# RP2040_MainV1_alternateLayout.net
KiCad netlist of a schematic drawn in EAGLE
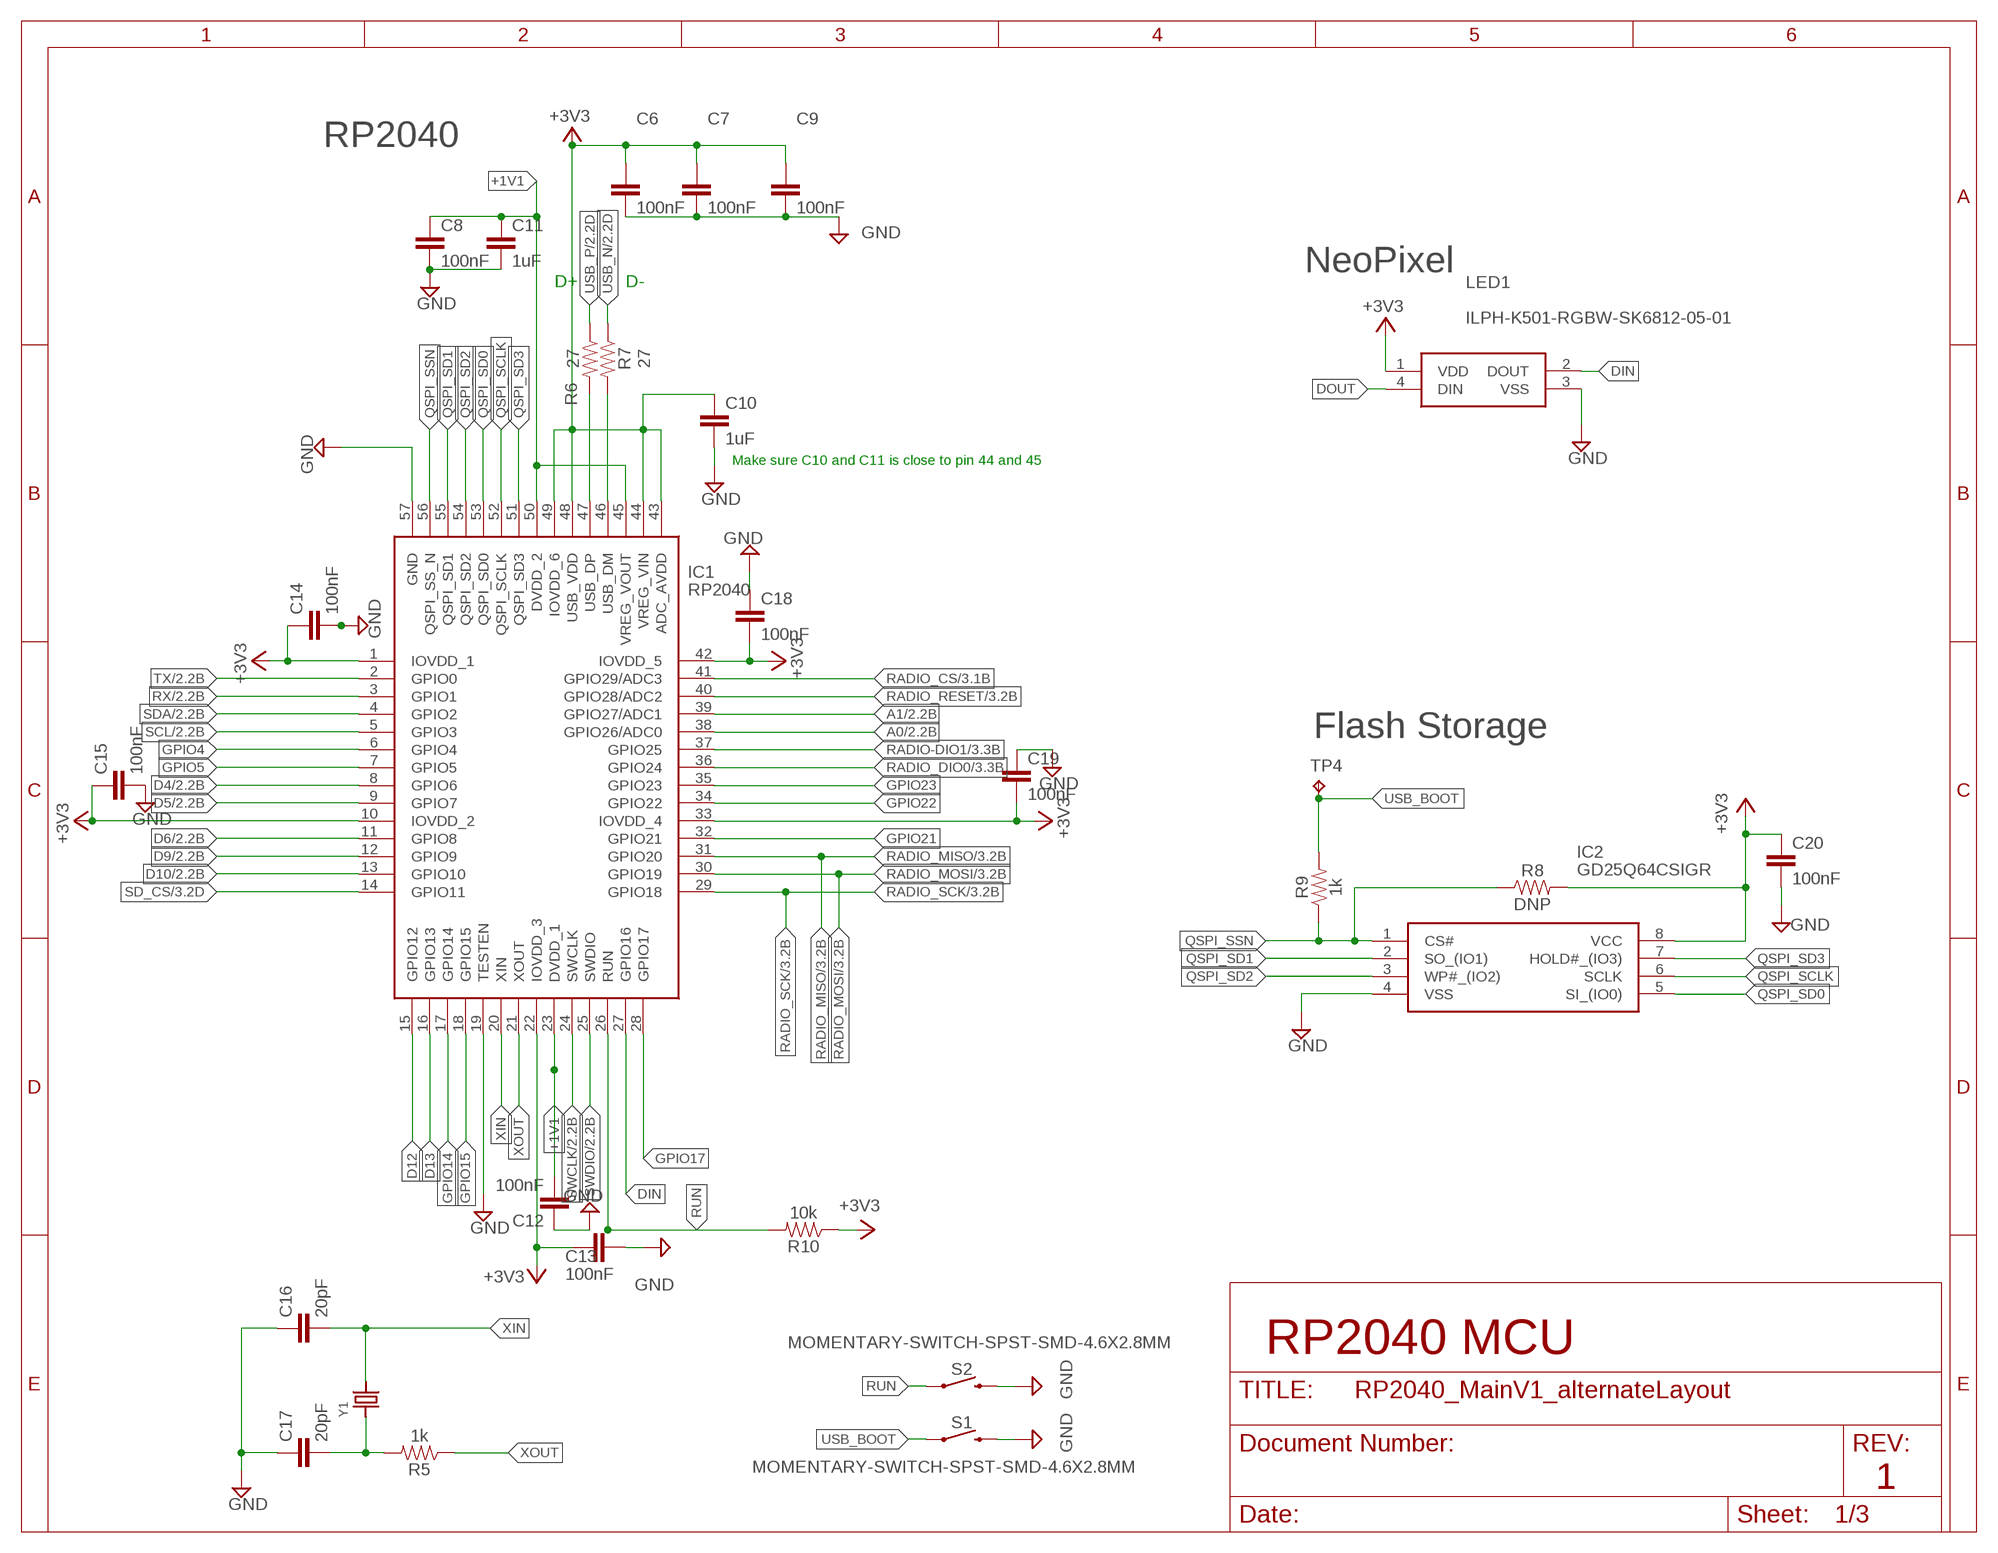
[diagram p0: schematic, sheet 1]
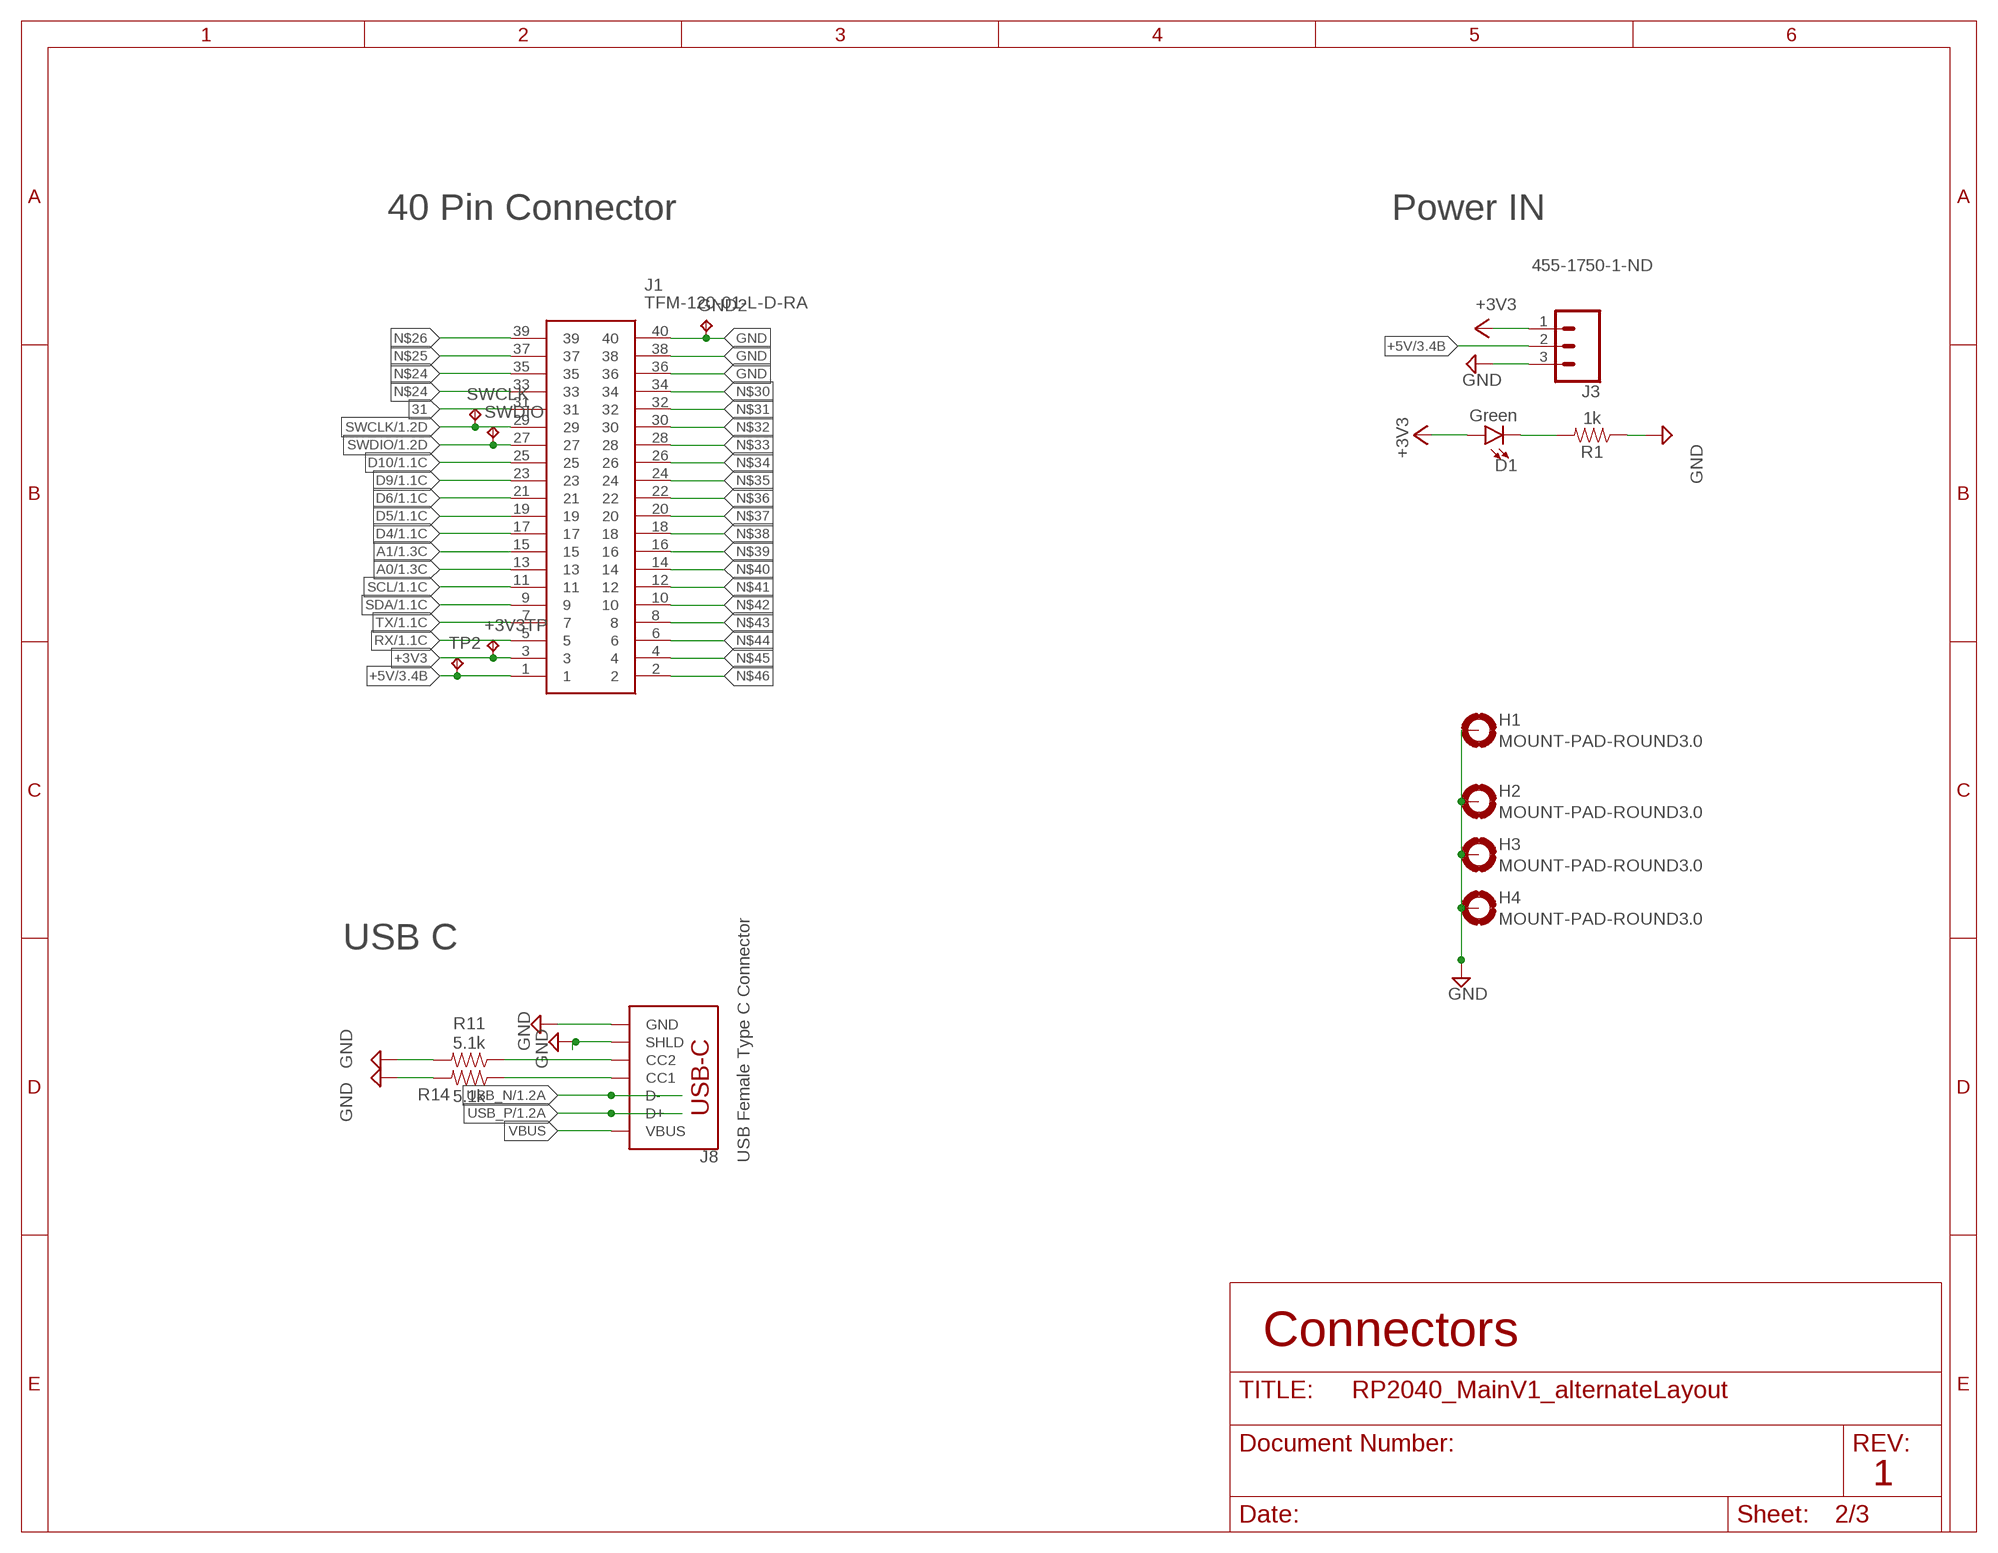
[diagram p1: schematic, sheet 2]
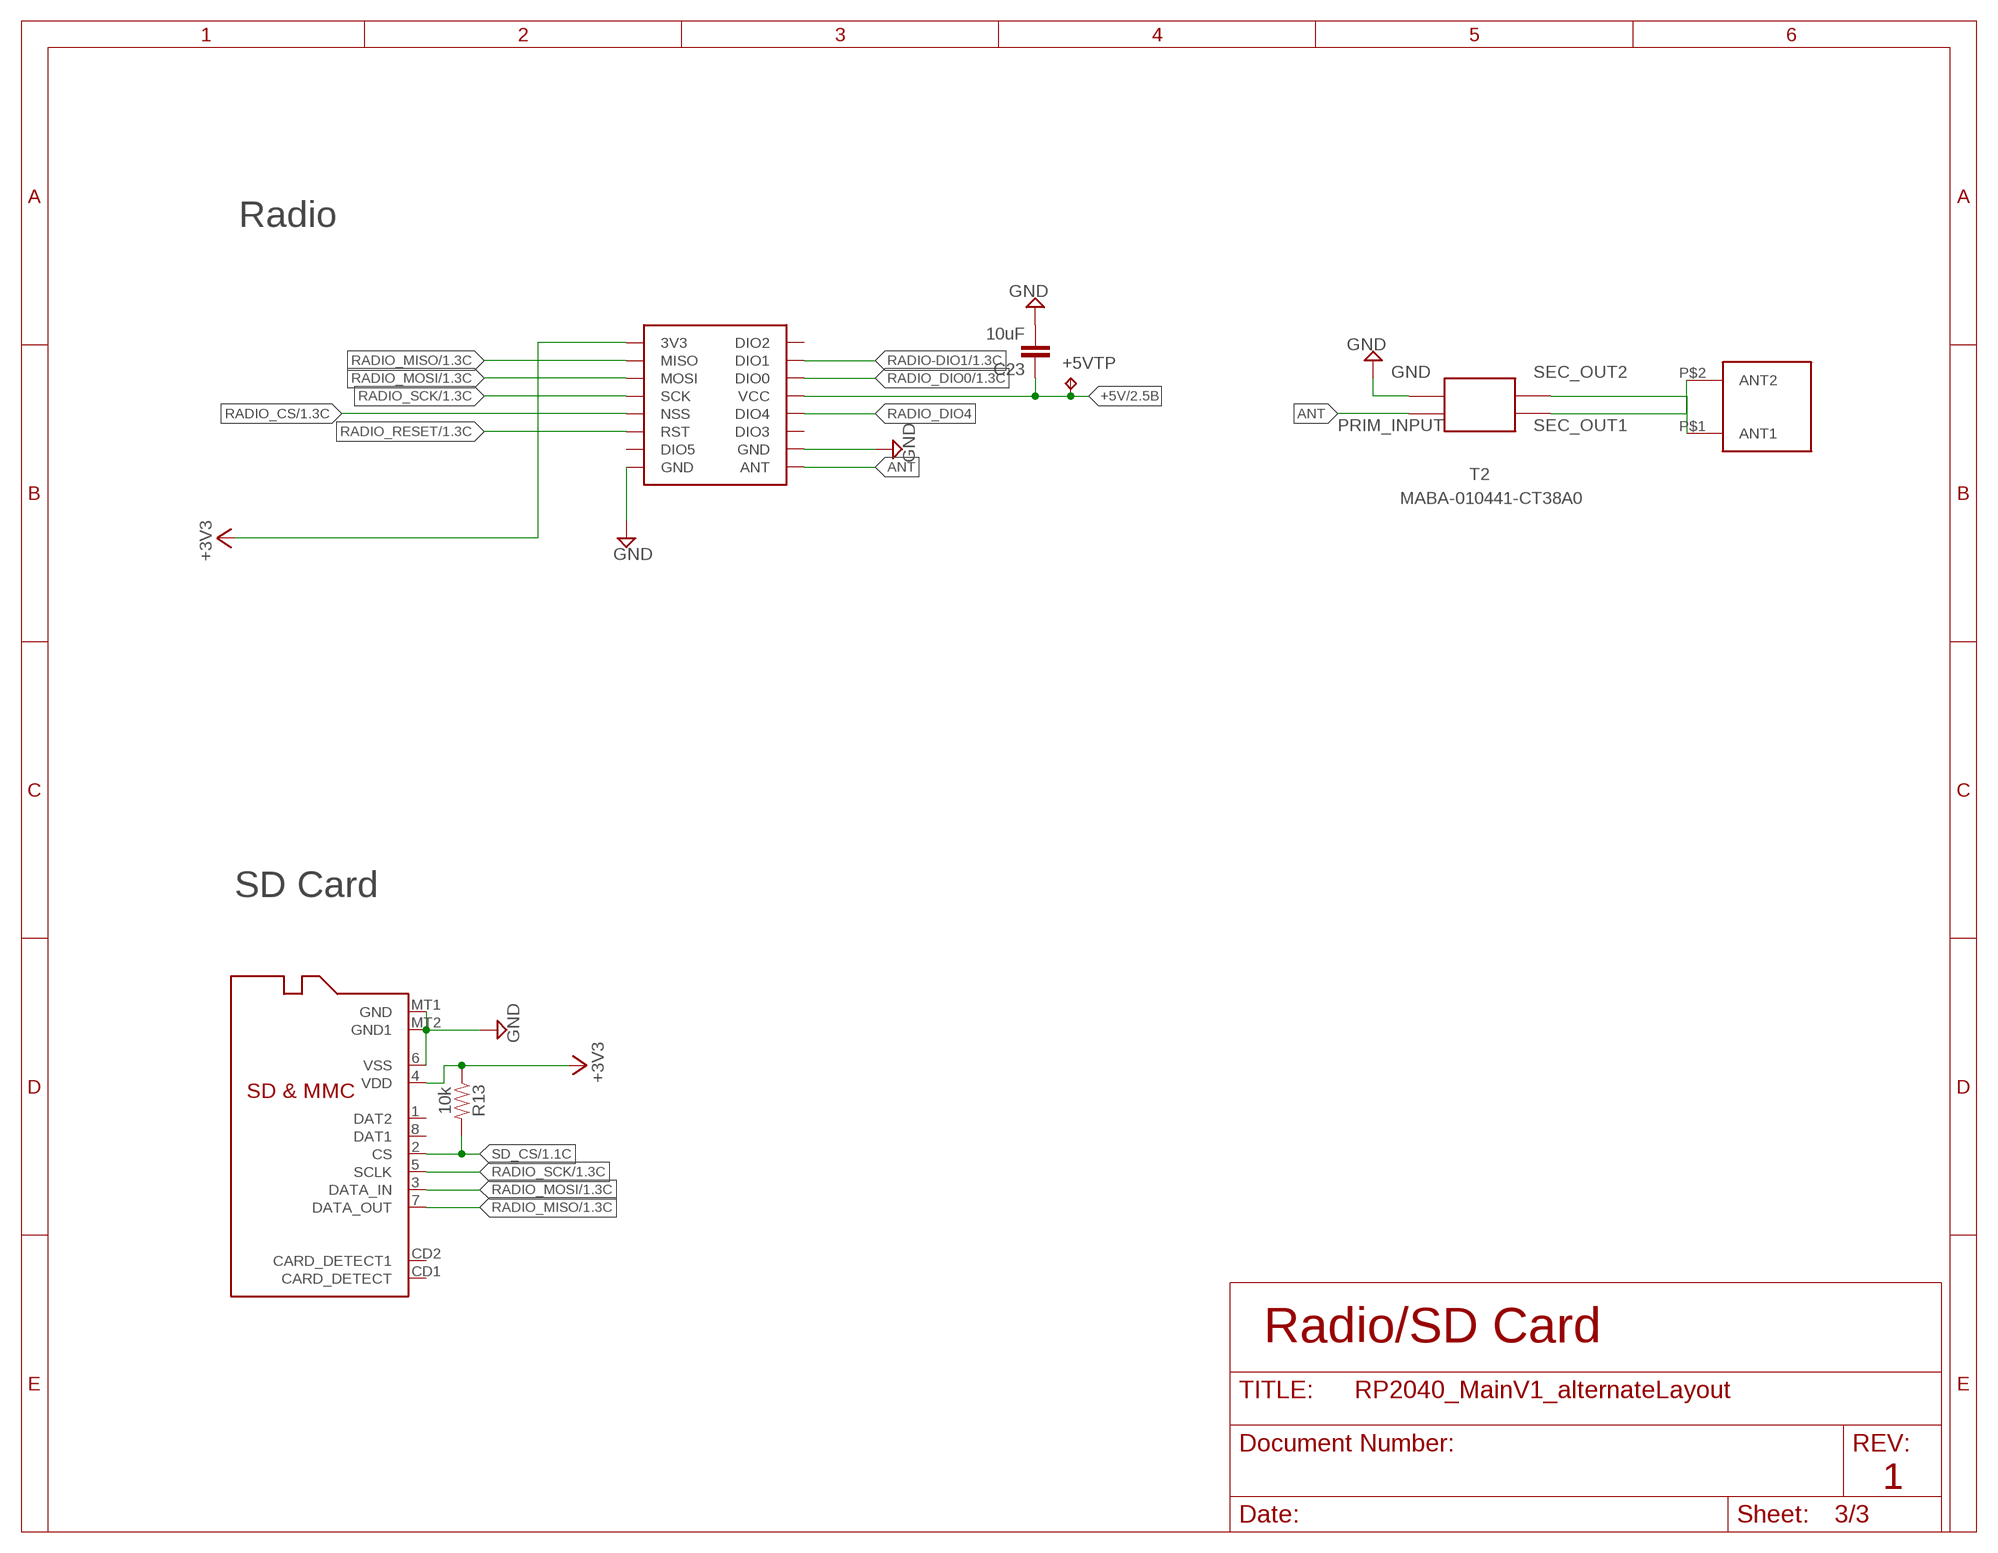
[diagram p2: schematic, sheet 3]

(export (version "E")
  (design (tool "Eeschema 10.0.6"))
  (components
    (comp (ref "C6")
      (value "100nF")
      (footprint "eagle-import:0402")
      (libsource (lib "eagle-import") (part "0.1UF-0402-10V-10%-X7R"))
    )
    (comp (ref "C7")
      (value "100nF")
      (footprint "eagle-import:0402")
      (libsource (lib "eagle-import") (part "0.1UF-0402-10V-10%-X7R"))
    )
    (comp (ref "C8")
      (value "100nF")
      (footprint "eagle-import:0402")
      (libsource (lib "eagle-import") (part "0.1UF-0402-10V-10%-X7R"))
    )
    (comp (ref "C9")
      (value "100nF")
      (footprint "eagle-import:0402")
      (libsource (lib "eagle-import") (part "0.1UF-0402-10V-10%-X7R"))
    )
    (comp (ref "C10")
      (value "1uF")
      (footprint "eagle-import:0402")
      (libsource (lib "eagle-import") (part "0.1UF-0402-10V-10%-X7R"))
    )
    (comp (ref "C11")
      (value "1uF")
      (footprint "eagle-import:0402")
      (libsource (lib "eagle-import") (part "0.1UF-0402-10V-10%-X7R"))
    )
    (comp (ref "C12")
      (value "100nF")
      (footprint "eagle-import:0402")
      (libsource (lib "eagle-import") (part "0.1UF-0402-10V-10%-X7R"))
    )
    (comp (ref "C13")
      (value "100nF")
      (footprint "eagle-import:0402")
      (libsource (lib "eagle-import") (part "0.1UF-0402-10V-10%-X7R"))
    )
    (comp (ref "C14")
      (value "100nF")
      (footprint "eagle-import:0402")
      (libsource (lib "eagle-import") (part "0.1UF-0402-10V-10%-X7R"))
    )
    (comp (ref "C15")
      (value "100nF")
      (footprint "eagle-import:0402")
      (libsource (lib "eagle-import") (part "0.1UF-0402-10V-10%-X7R"))
    )
    (comp (ref "C16")
      (value "20pF")
      (footprint "eagle-import:0603")
      (libsource (lib "eagle-import") (part "10NF-0603-50V-10%"))
    )
    (comp (ref "C17")
      (value "20pF")
      (footprint "eagle-import:0603")
      (libsource (lib "eagle-import") (part "10NF-0603-50V-10%"))
    )
    (comp (ref "C18")
      (value "100nF")
      (footprint "eagle-import:0402")
      (libsource (lib "eagle-import") (part "0.1UF-0402-10V-10%-X7R"))
    )
    (comp (ref "C19")
      (value "100nF")
      (footprint "eagle-import:0402")
      (libsource (lib "eagle-import") (part "0.1UF-0402-10V-10%-X7R"))
    )
    (comp (ref "C20")
      (value "100nF")
      (footprint "eagle-import:0603")
      (libsource (lib "eagle-import") (part "0.1UF-0603-25V-(+80/-20%)"))
    )
    (comp (ref "IC1")
      (value "RP2040")
      (footprint "eagle-import:QFN40P700X700X90-57N")
      (libsource (lib "eagle-import") (part "RP2040"))
    )
    (comp (ref "IC2")
      (value "GD25Q64CSIGR")
      (footprint "eagle-import:SOIC127P790X216-8N")
      (fields (field (name "MOUSER_PART_NUMBER") "363-GD25Q64CSIGR"))
      (libsource (lib "eagle-import") (part "GD25Q64CSIGR"))
    )
    (comp (ref "LED1")
      (value "ILPH-K501-RGBW-SK6812-05-01")
      (footprint "eagle-import:ILPHK501RGBWSK68120501")
      (libsource (lib "eagle-import") (part "ILPH-K501-RGBW-SK6812-05-01"))
    )
    (comp (ref "R5")
      (value "1k")
      (footprint "eagle-import:0603")
      (libsource (lib "eagle-import") (part "0.05OHM-0603-1/5W-1%"))
    )
    (comp (ref "R6")
      (value "27")
      (footprint "eagle-import:0603")
      (libsource (lib "eagle-import") (part "0.05OHM-0603-1/5W-1%"))
    )
    (comp (ref "R7")
      (value "27")
      (footprint "eagle-import:0603")
      (libsource (lib "eagle-import") (part "0.05OHM-0603-1/5W-1%"))
    )
    (comp (ref "R8")
      (value "DNP")
      (footprint "eagle-import:0603")
      (libsource (lib "eagle-import") (part "0.05OHM-0603-1/5W-1%"))
    )
    (comp (ref "R9")
      (value "1k")
      (footprint "eagle-import:0603")
      (libsource (lib "eagle-import") (part "0.05OHM-0603-1/5W-1%"))
    )
    (comp (ref "R10")
      (value "10k")
      (footprint "eagle-import:0603")
      (libsource (lib "eagle-import") (part "0.05OHM-0603-1/5W-1%"))
    )
    (comp (ref "S1")
      (value "MOMENTARY-SWITCH-SPST-SMD-4.6X2.8MM")
      (footprint "eagle-import:TACTILE_SWITCH_SMD_4.6X2.8MM")
      (libsource (lib "eagle-import") (part "MOMENTARY-SWITCH-SPST-SMD-4.6X2.8MM"))
    )
    (comp (ref "S2")
      (value "MOMENTARY-SWITCH-SPST-SMD-4.6X2.8MM")
      (footprint "eagle-import:TACTILE_SWITCH_SMD_4.6X2.8MM")
      (libsource (lib "eagle-import") (part "MOMENTARY-SWITCH-SPST-SMD-4.6X2.8MM"))
    )
    (comp (ref "TP4")
      (value "TPTP12R")
      (footprint "eagle-import:TP12R")
      (libsource (lib "eagle-import") (part "TPTP12R"))
    )
    (comp (ref "Y1")
      (value "CRYSTAL2.5X2.0MM")
      (footprint "eagle-import:CRYSTAL_2.5X2")
      (libsource (lib "eagle-import") (part "CRYSTAL2.5X2.0MM"))
    )
    (comp (ref "+3V3TP")
      (value "TPTP12R")
      (footprint "eagle-import:TP12R")
      (libsource (lib "eagle-import") (part "TPTP12R"))
    )
    (comp (ref "D1")
      (value "Green")
      (footprint "eagle-import:LED-0603")
      (libsource (lib "eagle-import") (part "LED-GREEN-0603-WE"))
    )
    (comp (ref "GND2")
      (value "TPTP12R")
      (footprint "eagle-import:TP12R")
      (libsource (lib "eagle-import") (part "TPTP12R"))
    )
    (comp (ref "H1")
      (value "MOUNT-PAD-ROUND3.0")
      (footprint "eagle-import:3,0-PAD")
      (libsource (lib "eagle-import") (part "MOUNT-PAD-ROUND3.0"))
    )
    (comp (ref "H2")
      (value "MOUNT-PAD-ROUND3.0")
      (footprint "eagle-import:3,0-PAD")
      (libsource (lib "eagle-import") (part "MOUNT-PAD-ROUND3.0"))
    )
    (comp (ref "H3")
      (value "MOUNT-PAD-ROUND3.0")
      (footprint "eagle-import:3,0-PAD")
      (libsource (lib "eagle-import") (part "MOUNT-PAD-ROUND3.0"))
    )
    (comp (ref "H4")
      (value "MOUNT-PAD-ROUND3.0")
      (footprint "eagle-import:3,0-PAD")
      (libsource (lib "eagle-import") (part "MOUNT-PAD-ROUND3.0"))
    )
    (comp (ref "J1")
      (value "TFM-120-01-L-D-RA")
      (footprint "eagle-import:TFM-120-01-XXX-D-RA")
      (fields (field (name "MOUSER_PART_NUMBER") "200-TFM12001LDRA"))
      (libsource (lib "eagle-import") (part "TFM-120-01-L-D-RA"))
    )
    (comp (ref "J3")
      (value "455-1750-1-ND")
      (footprint "eagle-import:1X03")
      (libsource (lib "eagle-import") (part "CONN_03"))
    )
    (comp (ref "J8")
      (value "USB Female Type C Connector")
      (footprint "eagle-import:USB-C-16P-4LAYER-ISOLATED")
      (libsource (lib "eagle-import") (part "USB_C_4-LAYER-ISOLATED"))
    )
    (comp (ref "R1")
      (value "1k")
      (footprint "eagle-import:0603")
      (libsource (lib "eagle-import") (part "0.05OHM-0603-1/5W-1%"))
    )
    (comp (ref "R11")
      (value "5.1k")
      (footprint "eagle-import:0603")
      (libsource (lib "eagle-import") (part "0.05OHM-0603-1/5W-1%"))
    )
    (comp (ref "R14")
      (value "5.1k")
      (footprint "eagle-import:0603")
      (libsource (lib "eagle-import") (part "0.05OHM-0603-1/5W-1%"))
    )
    (comp (ref "SWCLK")
      (value "TPTP12R")
      (footprint "eagle-import:TP12R")
      (libsource (lib "eagle-import") (part "TPTP12R"))
    )
    (comp (ref "SWDIO")
      (value "TPTP12R")
      (footprint "eagle-import:TP12R")
      (libsource (lib "eagle-import") (part "TPTP12R"))
    )
    (comp (ref "TP2")
      (value "TPTP12R")
      (footprint "eagle-import:TP12R")
      (libsource (lib "eagle-import") (part "TPTP12R"))
    )
    (comp (ref "+5VTP")
      (value "TPTP12R")
      (footprint "eagle-import:TP12R")
      (libsource (lib "eagle-import") (part "TPTP12R"))
    )
    (comp (ref "C23")
      (value "10uF")
      (footprint "eagle-import:0603")
      (libsource (lib "eagle-import") (part "10UF-0603-6.3V-20%"))
    )
    (comp (ref "R13")
      (value "10k")
      (footprint "eagle-import:0603")
      (libsource (lib "eagle-import") (part "0.05OHM-0603-1/5W-1%"))
    )
    (comp (ref "T2")
      (value "MABA-010441-CT38A0")
      (footprint "eagle-import:MABA010441CT38A0")
      (fields (field (name "MOUSER_PART_NUMBER") "937-MABA10441-CT38A0"))
      (libsource (lib "eagle-import") (part "MABA-010441-CT38A0"))
    )
    (comp (ref "U$1")
      (value "MICROSD")
      (footprint "eagle-import:MICROSD")
      (libsource (lib "eagle-import") (part "MICROSD"))
    )
    (comp (ref "U$2")
      (value "RFM95W")
      (footprint "eagle-import:RFM95PW")
      (libsource (lib "eagle-import") (part "RFM95W"))
    )
    (comp (ref "U$4")
      (value "BIGPAD")
      (footprint "eagle-import:BIGPADS")
      (libsource (lib "eagle-import") (part "BIGPAD"))
    )
  )
  (nets
    (net (code "1") (name "+1V1") (class "Default")
      (node (ref "C11") (pin "1") (pinfunction "1_1") (pintype "passive"))
      (node (ref "C12") (pin "2") (pinfunction "2_2") (pintype "passive"))
      (node (ref "C8") (pin "1") (pinfunction "1_1") (pintype "passive"))
      (node (ref "IC1") (pin "23") (pinfunction "DVDD_1_23") (pintype "bidirectional"))
      (node (ref "IC1") (pin "45") (pinfunction "VREG_VOUT_45") (pintype "bidirectional"))
      (node (ref "IC1") (pin "50") (pinfunction "DVDD_2_50") (pintype "bidirectional"))
    )
    (net (code "2") (name "+3V3") (class "Default")
      (node (ref "+3V3TP") (pin "TP") (pinfunction "TP_TP") (pintype "input"))
      (node (ref "C10") (pin "1") (pinfunction "1_1") (pintype "passive"))
      (node (ref "C13") (pin "2") (pinfunction "2_2") (pintype "passive"))
      (node (ref "C14") (pin "1") (pinfunction "1_1") (pintype "passive"))
      (node (ref "C15") (pin "1") (pinfunction "1_1") (pintype "passive"))
      (node (ref "C18") (pin "2") (pinfunction "2_2") (pintype "passive"))
      (node (ref "C19") (pin "2") (pinfunction "2_2") (pintype "passive"))
      (node (ref "C20") (pin "1") (pinfunction "1_1") (pintype "passive"))
      (node (ref "C6") (pin "1") (pinfunction "1_1") (pintype "passive"))
      (node (ref "C7") (pin "1") (pinfunction "1_1") (pintype "passive"))
      (node (ref "C9") (pin "1") (pinfunction "1_1") (pintype "passive"))
      (node (ref "D1") (pin "A") (pinfunction "A_A") (pintype "passive"))
      (node (ref "IC1") (pin "1") (pinfunction "IOVDD_1_1") (pintype "bidirectional"))
      (node (ref "IC1") (pin "10") (pinfunction "IOVDD_2_10") (pintype "bidirectional"))
      (node (ref "IC1") (pin "22") (pinfunction "IOVDD_3_22") (pintype "bidirectional"))
      (node (ref "IC1") (pin "33") (pinfunction "IOVDD_4_33") (pintype "bidirectional"))
      (node (ref "IC1") (pin "42") (pinfunction "IOVDD_5_42") (pintype "bidirectional"))
      (node (ref "IC1") (pin "43") (pinfunction "ADC_AVDD_43") (pintype "bidirectional"))
      (node (ref "IC1") (pin "44") (pinfunction "VREG_VIN_44") (pintype "bidirectional"))
      (node (ref "IC1") (pin "48") (pinfunction "USB_VDD_48") (pintype "bidirectional"))
      (node (ref "IC1") (pin "49") (pinfunction "IOVDD_6_49") (pintype "bidirectional"))
      (node (ref "IC2") (pin "8") (pinfunction "VCC_8") (pintype "bidirectional"))
      (node (ref "J1") (pin "3") (pinfunction "3_3") (pintype "bidirectional"))
      (node (ref "J3") (pin "1") (pinfunction "1_1") (pintype "passive"))
      (node (ref "LED1") (pin "1") (pinfunction "VDD_1") (pintype "bidirectional"))
      (node (ref "R10") (pin "1") (pinfunction "1_1") (pintype "passive"))
      (node (ref "R13") (pin "1") (pinfunction "1_1") (pintype "passive"))
      (node (ref "R8") (pin "2") (pinfunction "2_2") (pintype "passive"))
      (node (ref "U$1") (pin "4") (pinfunction "VDD_4") (pintype "power_in"))
      (node (ref "U$2") (pin "3V3") (pinfunction "3V3_3V3") (pintype "power_in"))
    )
    (net (code "3") (name "+5V") (class "Default")
      (node (ref "+5VTP") (pin "TP") (pinfunction "TP_TP") (pintype "input"))
      (node (ref "C23") (pin "1") (pinfunction "1_1") (pintype "passive"))
      (node (ref "J1") (pin "1") (pinfunction "1_1") (pintype "bidirectional"))
      (node (ref "J3") (pin "2") (pinfunction "2_2") (pintype "passive"))
      (node (ref "TP2") (pin "TP") (pinfunction "TP_TP") (pintype "input"))
      (node (ref "U$2") (pin "VCC") (pinfunction "VCC_VCC") (pintype "power_in"))
    )
    (net (code "4") (name "31") (class "Default")
      (node (ref "J1") (pin "31") (pinfunction "31_31") (pintype "bidirectional"))
    )
    (net (code "5") (name "A0") (class "Default")
      (node (ref "IC1") (pin "38") (pinfunction "GPIO26/ADC0_38") (pintype "bidirectional"))
      (node (ref "J1") (pin "13") (pinfunction "13_13") (pintype "bidirectional"))
    )
    (net (code "6") (name "A1") (class "Default")
      (node (ref "IC1") (pin "39") (pinfunction "GPIO27/ADC1_39") (pintype "bidirectional"))
      (node (ref "J1") (pin "15") (pinfunction "15_15") (pintype "bidirectional"))
    )
    (net (code "7") (name "ANT") (class "Default")
      (node (ref "T2") (pin "1") (pinfunction "PRIMARY_DOT_(INPUT)_1") (pintype "bidirectional"))
      (node (ref "U$2") (pin "ANT") (pinfunction "ANT_ANT") (pintype "bidirectional"))
    )
    (net (code "8") (name "D4") (class "Default")
      (node (ref "IC1") (pin "8") (pinfunction "GPIO6_8") (pintype "bidirectional"))
      (node (ref "J1") (pin "17") (pinfunction "17_17") (pintype "bidirectional"))
    )
    (net (code "9") (name "D5") (class "Default")
      (node (ref "IC1") (pin "9") (pinfunction "GPIO7_9") (pintype "bidirectional"))
      (node (ref "J1") (pin "19") (pinfunction "19_19") (pintype "bidirectional"))
    )
    (net (code "10") (name "D6") (class "Default")
      (node (ref "IC1") (pin "11") (pinfunction "GPIO8_11") (pintype "bidirectional"))
      (node (ref "J1") (pin "21") (pinfunction "21_21") (pintype "bidirectional"))
    )
    (net (code "11") (name "D9") (class "Default")
      (node (ref "IC1") (pin "12") (pinfunction "GPIO9_12") (pintype "bidirectional"))
      (node (ref "J1") (pin "23") (pinfunction "23_23") (pintype "bidirectional"))
    )
    (net (code "12") (name "D10") (class "Default")
      (node (ref "IC1") (pin "13") (pinfunction "GPIO10_13") (pintype "bidirectional"))
      (node (ref "J1") (pin "25") (pinfunction "25_25") (pintype "bidirectional"))
    )
    (net (code "13") (name "D12") (class "Default")
      (node (ref "IC1") (pin "15") (pinfunction "GPIO12_15") (pintype "bidirectional"))
    )
    (net (code "14") (name "D13") (class "Default")
      (node (ref "IC1") (pin "16") (pinfunction "GPIO13_16") (pintype "bidirectional"))
    )
    (net (code "15") (name "DIN") (class "Default")
      (node (ref "IC1") (pin "27") (pinfunction "GPIO16_27") (pintype "bidirectional"))
      (node (ref "LED1") (pin "2") (pinfunction "DOUT_2") (pintype "bidirectional"))
    )
    (net (code "16") (name "DOUT") (class "Default")
      (node (ref "LED1") (pin "4") (pinfunction "DIN_4") (pintype "bidirectional"))
    )
    (net (code "17") (name "GND") (class "Default")
      (node (ref "C10") (pin "2") (pinfunction "2_2") (pintype "passive"))
      (node (ref "C11") (pin "2") (pinfunction "2_2") (pintype "passive"))
      (node (ref "C12") (pin "1") (pinfunction "1_1") (pintype "passive"))
      (node (ref "C13") (pin "1") (pinfunction "1_1") (pintype "passive"))
      (node (ref "C14") (pin "2") (pinfunction "2_2") (pintype "passive"))
      (node (ref "C15") (pin "2") (pinfunction "2_2") (pintype "passive"))
      (node (ref "C16") (pin "1") (pinfunction "1_1") (pintype "passive"))
      (node (ref "C17") (pin "1") (pinfunction "1_1") (pintype "passive"))
      (node (ref "C18") (pin "1") (pinfunction "1_1") (pintype "passive"))
      (node (ref "C19") (pin "1") (pinfunction "1_1") (pintype "passive"))
      (node (ref "C20") (pin "2") (pinfunction "2_2") (pintype "passive"))
      (node (ref "C23") (pin "2") (pinfunction "2_2") (pintype "passive"))
      (node (ref "C6") (pin "2") (pinfunction "2_2") (pintype "passive"))
      (node (ref "C7") (pin "2") (pinfunction "2_2") (pintype "passive"))
      (node (ref "C8") (pin "2") (pinfunction "2_2") (pintype "passive"))
      (node (ref "C9") (pin "2") (pinfunction "2_2") (pintype "passive"))
      (node (ref "GND2") (pin "TP") (pinfunction "TP_TP") (pintype "input"))
      (node (ref "H1") (pin "B3,0") (pinfunction "MOUNT_B3,0") (pintype "passive"))
      (node (ref "H2") (pin "B3,0") (pinfunction "MOUNT_B3,0") (pintype "passive"))
      (node (ref "H3") (pin "B3,0") (pinfunction "MOUNT_B3,0") (pintype "passive"))
      (node (ref "H4") (pin "B3,0") (pinfunction "MOUNT_B3,0") (pintype "passive"))
      (node (ref "IC1") (pin "19") (pinfunction "TESTEN_19") (pintype "bidirectional"))
      (node (ref "IC1") (pin "57") (pinfunction "GND_57") (pintype "bidirectional"))
      (node (ref "IC2") (pin "4") (pinfunction "VSS_4") (pintype "bidirectional"))
      (node (ref "J1") (pin "36") (pinfunction "36_36") (pintype "bidirectional"))
      (node (ref "J1") (pin "38") (pinfunction "38_38") (pintype "bidirectional"))
      (node (ref "J1") (pin "40") (pinfunction "40_40") (pintype "bidirectional"))
      (node (ref "J3") (pin "3") (pinfunction "3_3") (pintype "passive"))
      (node (ref "J8") (pin "GND") (pinfunction "GND_GND") (pintype "bidirectional"))
      (node (ref "J8") (pin "GND2") (pinfunction "GND_GND2") (pintype "bidirectional"))
      (node (ref "J8") (pin "SHLD1") (pinfunction "SHLD_SHLD1") (pintype "bidirectional"))
      (node (ref "J8") (pin "SHLD2") (pinfunction "SHLD_SHLD2") (pintype "bidirectional"))
      (node (ref "J8") (pin "SHLD3") (pinfunction "SHLD_SHLD3") (pintype "bidirectional"))
      (node (ref "J8") (pin "SHLD4") (pinfunction "SHLD_SHLD4") (pintype "bidirectional"))
      (node (ref "J8") (pin "SHLD5") (pinfunction "SHLD_SHLD5") (pintype "bidirectional"))
      (node (ref "J8") (pin "SHLD6") (pinfunction "SHLD_SHLD6") (pintype "bidirectional"))
      (node (ref "J8") (pin "SHLD7") (pinfunction "SHLD_SHLD7") (pintype "bidirectional"))
      (node (ref "J8") (pin "SHLD8") (pinfunction "SHLD_SHLD8") (pintype "bidirectional"))
      (node (ref "LED1") (pin "3") (pinfunction "VSS_3") (pintype "bidirectional"))
      (node (ref "R1") (pin "1") (pinfunction "1_1") (pintype "passive"))
      (node (ref "R11") (pin "2") (pinfunction "2_2") (pintype "passive"))
      (node (ref "R14") (pin "2") (pinfunction "2_2") (pintype "passive"))
      (node (ref "S1") (pin "3") (pinfunction "2_3") (pintype "passive"))
      (node (ref "S1") (pin "4") (pinfunction "2_4") (pintype "passive"))
      (node (ref "S2") (pin "3") (pinfunction "2_3") (pintype "passive"))
      (node (ref "S2") (pin "4") (pinfunction "2_4") (pintype "passive"))
      (node (ref "T2") (pin "4") (pinfunction "PRIMARY_(GROUND)_4") (pintype "bidirectional"))
      (node (ref "U$1") (pin "6") (pinfunction "VSS_6") (pintype "power_in"))
      (node (ref "U$1") (pin "MT1") (pinfunction "GND_MT1") (pintype "power_in"))
      (node (ref "U$1") (pin "MT2") (pinfunction "GND1_MT2") (pintype "power_in"))
      (node (ref "U$2") (pin "GND@0") (pinfunction "GND_GND@0") (pintype "power_in"))
      (node (ref "U$2") (pin "GND@1") (pinfunction "GND_GND@1") (pintype "power_in"))
    )
    (net (code "18") (name "GPIO4") (class "Default")
      (node (ref "IC1") (pin "6") (pinfunction "GPIO4_6") (pintype "bidirectional"))
    )
    (net (code "19") (name "GPIO5") (class "Default")
      (node (ref "IC1") (pin "7") (pinfunction "GPIO5_7") (pintype "bidirectional"))
    )
    (net (code "20") (name "GPIO14") (class "Default")
      (node (ref "IC1") (pin "17") (pinfunction "GPIO14_17") (pintype "bidirectional"))
    )
    (net (code "21") (name "GPIO15") (class "Default")
      (node (ref "IC1") (pin "18") (pinfunction "GPIO15_18") (pintype "bidirectional"))
    )
    (net (code "22") (name "GPIO17") (class "Default")
      (node (ref "IC1") (pin "28") (pinfunction "GPIO17_28") (pintype "bidirectional"))
    )
    (net (code "23") (name "GPIO21") (class "Default")
      (node (ref "IC1") (pin "32") (pinfunction "GPIO21_32") (pintype "bidirectional"))
    )
    (net (code "24") (name "GPIO22") (class "Default")
      (node (ref "IC1") (pin "34") (pinfunction "GPIO22_34") (pintype "bidirectional"))
    )
    (net (code "25") (name "GPIO23") (class "Default")
      (node (ref "IC1") (pin "35") (pinfunction "GPIO23_35") (pintype "bidirectional"))
    )
    (net (code "26") (name "N$24") (class "Default")
      (node (ref "J1") (pin "35") (pinfunction "35_35") (pintype "bidirectional"))
    )
    (net (code "27") (name "N$25") (class "Default")
      (node (ref "J1") (pin "37") (pinfunction "37_37") (pintype "bidirectional"))
    )
    (net (code "28") (name "N$26") (class "Default")
      (node (ref "J1") (pin "39") (pinfunction "39_39") (pintype "bidirectional"))
    )
    (net (code "29") (name "N$30") (class "Default")
      (node (ref "J1") (pin "34") (pinfunction "34_34") (pintype "bidirectional"))
    )
    (net (code "30") (name "N$31") (class "Default")
      (node (ref "J1") (pin "32") (pinfunction "32_32") (pintype "bidirectional"))
    )
    (net (code "31") (name "N$32") (class "Default")
      (node (ref "J1") (pin "30") (pinfunction "30_30") (pintype "bidirectional"))
    )
    (net (code "32") (name "N$33") (class "Default")
      (node (ref "J1") (pin "28") (pinfunction "28_28") (pintype "bidirectional"))
    )
    (net (code "33") (name "N$34") (class "Default")
      (node (ref "J1") (pin "26") (pinfunction "26_26") (pintype "bidirectional"))
    )
    (net (code "34") (name "N$35") (class "Default")
      (node (ref "J1") (pin "24") (pinfunction "24_24") (pintype "bidirectional"))
    )
    (net (code "35") (name "N$36") (class "Default")
      (node (ref "J1") (pin "22") (pinfunction "22_22") (pintype "bidirectional"))
    )
    (net (code "36") (name "N$37") (class "Default")
      (node (ref "J1") (pin "20") (pinfunction "20_20") (pintype "bidirectional"))
    )
    (net (code "37") (name "N$38") (class "Default")
      (node (ref "J1") (pin "18") (pinfunction "18_18") (pintype "bidirectional"))
    )
    (net (code "38") (name "N$39") (class "Default")
      (node (ref "J1") (pin "16") (pinfunction "16_16") (pintype "bidirectional"))
    )
    (net (code "39") (name "N$40") (class "Default")
      (node (ref "J1") (pin "14") (pinfunction "14_14") (pintype "bidirectional"))
    )
    (net (code "40") (name "N$41") (class "Default")
      (node (ref "J1") (pin "12") (pinfunction "12_12") (pintype "bidirectional"))
    )
    (net (code "41") (name "N$42") (class "Default")
      (node (ref "J1") (pin "10") (pinfunction "10_10") (pintype "bidirectional"))
    )
    (net (code "42") (name "N$43") (class "Default")
      (node (ref "J1") (pin "8") (pinfunction "8_8") (pintype "bidirectional"))
    )
    (net (code "43") (name "N$44") (class "Default")
      (node (ref "J1") (pin "6") (pinfunction "6_6") (pintype "bidirectional"))
    )
    (net (code "44") (name "N$45") (class "Default")
      (node (ref "J1") (pin "4") (pinfunction "4_4") (pintype "bidirectional"))
    )
    (net (code "45") (name "N$46") (class "Default")
      (node (ref "J1") (pin "2") (pinfunction "2_2") (pintype "bidirectional"))
    )
    (net (code "46") (name "Net-(C17-Pad2)") (class "Default")
      (node (ref "C17") (pin "2") (pinfunction "2_2") (pintype "passive"))
      (node (ref "R5") (pin "2") (pinfunction "2_2") (pintype "passive"))
      (node (ref "Y1") (pin "1") (pinfunction "1_1") (pintype "passive"))
    )
    (net (code "47") (name "Net-(D1-PadC)") (class "Default")
      (node (ref "D1") (pin "C") (pinfunction "C_C") (pintype "passive"))
      (node (ref "R1") (pin "2") (pinfunction "2_2") (pintype "passive"))
    )
    (net (code "48") (name "Net-(IC1-USB_DM)") (class "Default")
      (node (ref "IC1") (pin "46") (pinfunction "USB_DM_46") (pintype "bidirectional"))
      (node (ref "R7") (pin "2") (pinfunction "2_2") (pintype "passive"))
    )
    (net (code "49") (name "Net-(IC1-USB_DP)") (class "Default")
      (node (ref "IC1") (pin "47") (pinfunction "USB_DP_47") (pintype "bidirectional"))
      (node (ref "R6") (pin "2") (pinfunction "2_2") (pintype "passive"))
    )
    (net (code "50") (name "Net-(J8-CC1)") (class "Default")
      (node (ref "J8") (pin "A5") (pinfunction "CC1_A5") (pintype "bidirectional"))
      (node (ref "R14") (pin "1") (pinfunction "1_1") (pintype "passive"))
    )
    (net (code "51") (name "Net-(J8-CC2)") (class "Default")
      (node (ref "J8") (pin "B5") (pinfunction "CC2_B5") (pintype "bidirectional"))
      (node (ref "R11") (pin "1") (pinfunction "1_1") (pintype "passive"))
    )
    (net (code "52") (name "Net-(T2-SECONDARY_(OUTPUT_2))") (class "Default")
      (node (ref "T2") (pin "3") (pinfunction "SECONDARY_(OUTPUT_2)_3") (pintype "bidirectional"))
      (node (ref "U$4") (pin "P$1") (pinfunction "ANT1_P$1") (pintype "bidirectional"))
    )
    (net (code "53") (name "Net-(T2-SECONDARY_DOT_(OUTPUT_1))") (class "Default")
      (node (ref "T2") (pin "2") (pinfunction "SECONDARY_DOT_(OUTPUT_1)_2") (pintype "bidirectional"))
      (node (ref "U$4") (pin "P$2") (pinfunction "ANT2_P$2") (pintype "bidirectional"))
    )
    (net (code "54") (name "QSPI_SCLK") (class "Default")
      (node (ref "IC1") (pin "52") (pinfunction "QSPI_SCLK_52") (pintype "bidirectional"))
      (node (ref "IC2") (pin "6") (pinfunction "SCLK_6") (pintype "bidirectional"))
    )
    (net (code "55") (name "QSPI_SD0") (class "Default")
      (node (ref "IC1") (pin "53") (pinfunction "QSPI_SD0_53") (pintype "bidirectional"))
      (node (ref "IC2") (pin "5") (pinfunction "SI_(IO0)_5") (pintype "bidirectional"))
    )
    (net (code "56") (name "QSPI_SD1") (class "Default")
      (node (ref "IC1") (pin "55") (pinfunction "QSPI_SD1_55") (pintype "bidirectional"))
      (node (ref "IC2") (pin "2") (pinfunction "SO_(IO1)_2") (pintype "bidirectional"))
    )
    (net (code "57") (name "QSPI_SD2") (class "Default")
      (node (ref "IC1") (pin "54") (pinfunction "QSPI_SD2_54") (pintype "bidirectional"))
      (node (ref "IC2") (pin "3") (pinfunction "WP#_(IO2)_3") (pintype "bidirectional"))
    )
    (net (code "58") (name "QSPI_SD3") (class "Default")
      (node (ref "IC1") (pin "51") (pinfunction "QSPI_SD3_51") (pintype "bidirectional"))
      (node (ref "IC2") (pin "7") (pinfunction "HOLD#_(IO3)_7") (pintype "bidirectional"))
    )
    (net (code "59") (name "QSPI_SSN") (class "Default")
      (node (ref "IC1") (pin "56") (pinfunction "QSPI_SS_N_56") (pintype "bidirectional"))
      (node (ref "IC2") (pin "1") (pinfunction "CS#_1") (pintype "bidirectional"))
      (node (ref "R8") (pin "1") (pinfunction "1_1") (pintype "passive"))
      (node (ref "R9") (pin "1") (pinfunction "1_1") (pintype "passive"))
    )
    (net (code "60") (name "RADIO-DIO1") (class "Default")
      (node (ref "IC1") (pin "37") (pinfunction "GPIO25_37") (pintype "bidirectional"))
      (node (ref "U$2") (pin "DIO1") (pinfunction "DIO1_DIO1") (pintype "bidirectional"))
    )
    (net (code "61") (name "RADIO_CS") (class "Default")
      (node (ref "IC1") (pin "41") (pinfunction "GPIO29/ADC3_41") (pintype "bidirectional"))
      (node (ref "U$2") (pin "NSS") (pinfunction "NSS_NSS") (pintype "bidirectional"))
    )
    (net (code "62") (name "RADIO_DIO0") (class "Default")
      (node (ref "IC1") (pin "36") (pinfunction "GPIO24_36") (pintype "bidirectional"))
      (node (ref "U$2") (pin "DIO0") (pinfunction "DIO0_DIO0") (pintype "bidirectional"))
    )
    (net (code "63") (name "RADIO_DIO4") (class "Default")
      (node (ref "U$2") (pin "DIO4") (pinfunction "DIO4_DIO4") (pintype "bidirectional"))
    )
    (net (code "64") (name "RADIO_MISO") (class "Default")
      (node (ref "IC1") (pin "31") (pinfunction "GPIO20_31") (pintype "bidirectional"))
      (node (ref "U$1") (pin "7") (pinfunction "DATA_OUT_7") (pintype "output"))
      (node (ref "U$2") (pin "MISO") (pinfunction "MISO_MISO") (pintype "bidirectional"))
    )
    (net (code "65") (name "RADIO_MOSI") (class "Default")
      (node (ref "IC1") (pin "30") (pinfunction "GPIO19_30") (pintype "bidirectional"))
      (node (ref "U$1") (pin "3") (pinfunction "DATA_IN_3") (pintype "input"))
      (node (ref "U$2") (pin "MOSI") (pinfunction "MOSI_MOSI") (pintype "bidirectional"))
    )
    (net (code "66") (name "RADIO_RESET") (class "Default")
      (node (ref "IC1") (pin "40") (pinfunction "GPIO28/ADC2_40") (pintype "bidirectional"))
      (node (ref "U$2") (pin "RST") (pinfunction "RST_RST") (pintype "bidirectional"))
    )
    (net (code "67") (name "RADIO_SCK") (class "Default")
      (node (ref "IC1") (pin "29") (pinfunction "GPIO18_29") (pintype "bidirectional"))
      (node (ref "U$1") (pin "5") (pinfunction "SCLK_5") (pintype "input"))
      (node (ref "U$2") (pin "SCK") (pinfunction "SCK_SCK") (pintype "bidirectional"))
    )
    (net (code "68") (name "RUN") (class "Default")
      (node (ref "IC1") (pin "26") (pinfunction "RUN_26") (pintype "bidirectional"))
      (node (ref "R10") (pin "2") (pinfunction "2_2") (pintype "passive"))
      (node (ref "S2") (pin "1") (pinfunction "1_1") (pintype "passive"))
      (node (ref "S2") (pin "2") (pinfunction "1_2") (pintype "passive"))
    )
    (net (code "69") (name "RX") (class "Default")
      (node (ref "IC1") (pin "3") (pinfunction "GPIO1_3") (pintype "bidirectional"))
      (node (ref "J1") (pin "5") (pinfunction "5_5") (pintype "bidirectional"))
    )
    (net (code "70") (name "SCL") (class "Default")
      (node (ref "IC1") (pin "5") (pinfunction "GPIO3_5") (pintype "bidirectional"))
      (node (ref "J1") (pin "11") (pinfunction "11_11") (pintype "bidirectional"))
    )
    (net (code "71") (name "SDA") (class "Default")
      (node (ref "IC1") (pin "4") (pinfunction "GPIO2_4") (pintype "bidirectional"))
      (node (ref "J1") (pin "9") (pinfunction "9_9") (pintype "bidirectional"))
    )
    (net (code "72") (name "SD_CS") (class "Default")
      (node (ref "IC1") (pin "14") (pinfunction "GPIO11_14") (pintype "bidirectional"))
      (node (ref "R13") (pin "2") (pinfunction "2_2") (pintype "passive"))
      (node (ref "U$1") (pin "2") (pinfunction "CS_2") (pintype "input"))
    )
    (net (code "73") (name "SWCLK") (class "Default")
      (node (ref "IC1") (pin "24") (pinfunction "SWCLK_24") (pintype "bidirectional"))
      (node (ref "J1") (pin "29") (pinfunction "29_29") (pintype "bidirectional"))
      (node (ref "SWCLK") (pin "TP") (pinfunction "TP_TP") (pintype "input"))
    )
    (net (code "74") (name "SWDIO") (class "Default")
      (node (ref "IC1") (pin "25") (pinfunction "SWDIO_25") (pintype "bidirectional"))
      (node (ref "J1") (pin "27") (pinfunction "27_27") (pintype "bidirectional"))
      (node (ref "SWDIO") (pin "TP") (pinfunction "TP_TP") (pintype "input"))
    )
    (net (code "75") (name "TX") (class "Default")
      (node (ref "IC1") (pin "2") (pinfunction "GPIO0_2") (pintype "bidirectional"))
      (node (ref "J1") (pin "7") (pinfunction "7_7") (pintype "bidirectional"))
    )
    (net (code "76") (name "USB_BOOT") (class "Default")
      (node (ref "R9") (pin "2") (pinfunction "2_2") (pintype "passive"))
      (node (ref "S1") (pin "1") (pinfunction "1_1") (pintype "passive"))
      (node (ref "S1") (pin "2") (pinfunction "1_2") (pintype "passive"))
      (node (ref "TP4") (pin "TP") (pinfunction "TP_TP") (pintype "input"))
    )
    (net (code "77") (name "USB_N") (class "Default")
      (node (ref "J8") (pin "A7") (pinfunction "D-_A7") (pintype "bidirectional"))
      (node (ref "J8") (pin "B7") (pinfunction "D-_B7") (pintype "bidirectional"))
      (node (ref "R7") (pin "1") (pinfunction "1_1") (pintype "passive"))
    )
    (net (code "78") (name "USB_P") (class "Default")
      (node (ref "J8") (pin "A6") (pinfunction "D+_A6") (pintype "bidirectional"))
      (node (ref "J8") (pin "B6") (pinfunction "D+_B6") (pintype "bidirectional"))
      (node (ref "R6") (pin "1") (pinfunction "1_1") (pintype "passive"))
    )
    (net (code "79") (name "VBUS") (class "Default")
      (node (ref "J8") (pin "VBUS1") (pinfunction "VBUS_VBUS1") (pintype "bidirectional"))
      (node (ref "J8") (pin "VBUS2") (pinfunction "VBUS_VBUS2") (pintype "bidirectional"))
    )
    (net (code "80") (name "XIN") (class "Default")
      (node (ref "C16") (pin "2") (pinfunction "2_2") (pintype "passive"))
      (node (ref "IC1") (pin "20") (pinfunction "XIN_20") (pintype "bidirectional"))
      (node (ref "Y1") (pin "3") (pinfunction "2_3") (pintype "passive"))
    )
    (net (code "81") (name "XOUT") (class "Default")
      (node (ref "IC1") (pin "21") (pinfunction "XOUT_21") (pintype "bidirectional"))
      (node (ref "R5") (pin "1") (pinfunction "1_1") (pintype "passive"))
    )
    (net (code "82") (name "unconnected-(J1-Pad33)") (class "Default")
      (node (ref "J1") (pin "33") (pinfunction "33_33") (pintype "bidirectional"))
    )
    (net (code "83") (name "unconnected-(U$1-CARD_DETECT-PadCD1)") (class "Default")
      (node (ref "U$1") (pin "CD1") (pinfunction "CARD_DETECT_CD1") (pintype "passive"))
    )
    (net (code "84") (name "unconnected-(U$1-CARD_DETECT1-PadCD2)") (class "Default")
      (node (ref "U$1") (pin "CD2") (pinfunction "CARD_DETECT1_CD2") (pintype "passive"))
    )
    (net (code "85") (name "unconnected-(U$1-DAT1-Pad8)") (class "Default")
      (node (ref "U$1") (pin "8") (pinfunction "DAT1_8") (pintype "bidirectional"))
    )
    (net (code "86") (name "unconnected-(U$1-DAT2-Pad1)") (class "Default")
      (node (ref "U$1") (pin "1") (pinfunction "DAT2_1") (pintype "bidirectional"))
    )
    (net (code "87") (name "unconnected-(U$2-PadDIO2)") (class "Default")
      (node (ref "U$2") (pin "DIO2") (pinfunction "DIO2_DIO2") (pintype "bidirectional"))
    )
    (net (code "88") (name "unconnected-(U$2-PadDIO3)") (class "Default")
      (node (ref "U$2") (pin "DIO3") (pinfunction "DIO3_DIO3") (pintype "bidirectional"))
    )
    (net (code "89") (name "unconnected-(U$2-PadDIO5)") (class "Default")
      (node (ref "U$2") (pin "DIO5") (pinfunction "DIO5_DIO5") (pintype "bidirectional"))
    )
  )
)
